# InputDevice.net
KiCad netlist of a schematic drawn in EAGLE
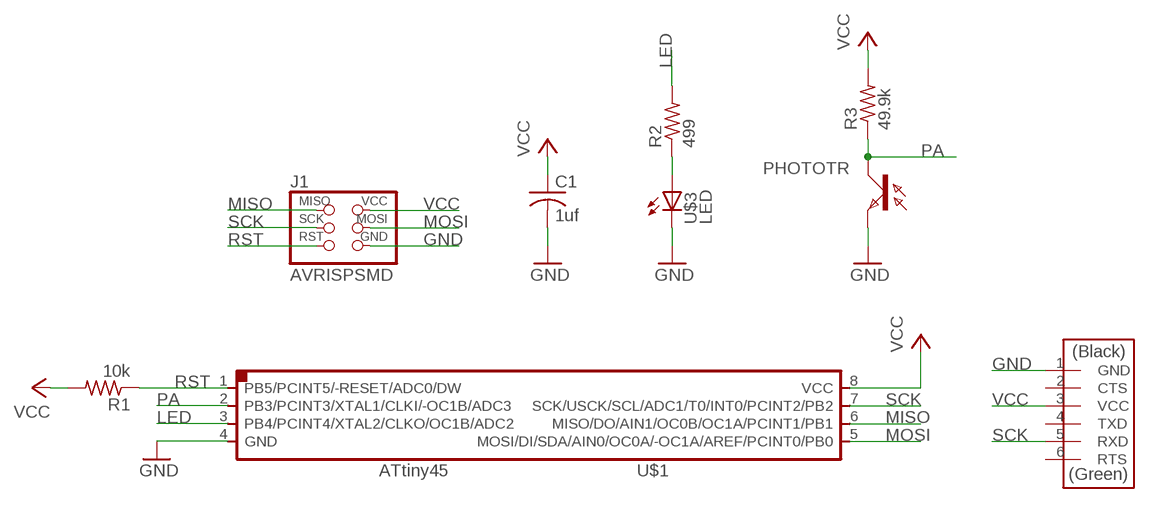
[diagram p0: schematic, sheet 1]

(export (version "E")
  (design (tool "Eeschema 10.0.6"))
  (components
    (comp (ref "C1")
      (value "1uf")
      (footprint "eagle-import:C1206")
      (libsource (lib "eagle-import") (part "C-USC1206"))
    )
    (comp (ref "J1")
      (value "AVRISPSMD")
      (footprint "eagle-import:2X03SMD")
      (libsource (lib "eagle-import") (part "AVRISPSMD"))
    )
    (comp (ref "PHOTOTR")
      (value "PHOTOTRANSISTOR-NPN1206")
      (footprint "eagle-import:OP1206")
      (libsource (lib "eagle-import") (part "PHOTOTRANSISTOR-NPN1206"))
    )
    (comp (ref "R1")
      (value "10k")
      (footprint "eagle-import:R1206")
      (libsource (lib "eagle-import") (part "R-US_R1206"))
    )
    (comp (ref "R2")
      (value "499")
      (footprint "eagle-import:1206")
      (libsource (lib "eagle-import") (part "RESISTOR1206"))
    )
    (comp (ref "R3")
      (value "49.9k")
      (footprint "eagle-import:1206")
      (libsource (lib "eagle-import") (part "RESISTOR1206"))
    )
    (comp (ref "U$1")
      (value "ATTINY45SI")
      (footprint "eagle-import:SOIC8")
      (libsource (lib "eagle-import") (part "ATTINY45SI"))
    )
    (comp (ref "U$3")
      (value "LED")
      (footprint "eagle-import:1206")
      (libsource (lib "eagle-import") (part "LED1206"))
    )
    (comp (ref "U$4")
      (value "FTDI-SMD-HEADER")
      (footprint "eagle-import:1X06SMD")
      (libsource (lib "eagle-import") (part "FTDI-SMD-HEADER"))
    )
  )
  (nets
    (net (code "1") (name "/LED") (class "Default")
      (node (ref "R2") (pin "2") (pinfunction "2_2") (pintype "passive"))
      (node (ref "U$1") (pin "3") (pinfunction "PB4/PCINT4/XTAL2/CLKO/OC1B/ADC2_3") (pintype "bidirectional"))
    )
    (net (code "2") (name "/MISO") (class "Default")
      (node (ref "J1") (pin "1") (pinfunction "MISO_1") (pintype "passive"))
      (node (ref "U$1") (pin "6") (pinfunction "MISO/DO/AIN1/OC0B/OC1A/PCINT1/PB1_6") (pintype "bidirectional"))
    )
    (net (code "3") (name "/MOSI") (class "Default")
      (node (ref "J1") (pin "4") (pinfunction "MOSI_4") (pintype "passive"))
      (node (ref "U$1") (pin "5") (pinfunction "MOSI/DI/SDA/AIN0/OC0A/-OC1A/AREF/PCINT0/PB0_5") (pintype "bidirectional"))
    )
    (net (code "4") (name "/PA") (class "Default")
      (node (ref "PHOTOTR") (pin "COLLECTOR") (pinfunction "C_COLLECTOR") (pintype "passive"))
      (node (ref "R3") (pin "1") (pinfunction "1_1") (pintype "passive"))
      (node (ref "U$1") (pin "2") (pinfunction "PB3/PCINT3/XTAL1/CLKI/-OC1B/ADC3_2") (pintype "bidirectional"))
    )
    (net (code "5") (name "/RST") (class "Default")
      (node (ref "J1") (pin "5") (pinfunction "RST_5") (pintype "passive"))
      (node (ref "R1") (pin "1") (pinfunction "1_1") (pintype "passive"))
      (node (ref "U$1") (pin "1") (pinfunction "PB5/PCINT5/-RESET/ADC0/DW_1") (pintype "bidirectional"))
    )
    (net (code "6") (name "/SCK") (class "Default")
      (node (ref "J1") (pin "3") (pinfunction "SCK_3") (pintype "passive"))
      (node (ref "U$1") (pin "7") (pinfunction "SCK/USCK/SCL/ADC1/T0/INT0/PCINT2/PB2_7") (pintype "bidirectional"))
      (node (ref "U$4") (pin "5") (pinfunction "RXD_5") (pintype "bidirectional"))
    )
    (net (code "7") (name "GND") (class "Default")
      (node (ref "C1") (pin "2") (pinfunction "2_2") (pintype "passive"))
      (node (ref "J1") (pin "6") (pinfunction "GND_6") (pintype "passive"))
      (node (ref "PHOTOTR") (pin "EMITTER") (pinfunction "E_EMITTER") (pintype "passive"))
      (node (ref "U$1") (pin "4") (pinfunction "GND_4") (pintype "bidirectional"))
      (node (ref "U$3") (pin "2") (pinfunction "C_2") (pintype "passive"))
      (node (ref "U$4") (pin "1") (pinfunction "GND_1") (pintype "bidirectional"))
    )
    (net (code "8") (name "Net-(U$3-A)") (class "Default")
      (node (ref "R2") (pin "1") (pinfunction "1_1") (pintype "passive"))
      (node (ref "U$3") (pin "1") (pinfunction "A_1") (pintype "passive"))
    )
    (net (code "9") (name "VCC") (class "Default")
      (node (ref "C1") (pin "1") (pinfunction "1_1") (pintype "passive"))
      (node (ref "J1") (pin "2") (pinfunction "VCC_2") (pintype "passive"))
      (node (ref "R1") (pin "2") (pinfunction "2_2") (pintype "passive"))
      (node (ref "R3") (pin "2") (pinfunction "2_2") (pintype "passive"))
      (node (ref "U$1") (pin "8") (pinfunction "VCC_8") (pintype "bidirectional"))
      (node (ref "U$4") (pin "3") (pinfunction "VCC_3") (pintype "bidirectional"))
    )
    (net (code "10") (name "unconnected-(U$4-CTS-Pad2)") (class "Default")
      (node (ref "U$4") (pin "2") (pinfunction "CTS_2") (pintype "bidirectional"))
    )
    (net (code "11") (name "unconnected-(U$4-RTS-Pad6)") (class "Default")
      (node (ref "U$4") (pin "6") (pinfunction "RTS_6") (pintype "bidirectional"))
    )
    (net (code "12") (name "unconnected-(U$4-TXD-Pad4)") (class "Default")
      (node (ref "U$4") (pin "4") (pinfunction "TXD_4") (pintype "bidirectional"))
    )
  )
)
